# Mobile_Tracker_Hat.net
KiCad netlist of a schematic drawn in Altium Designer
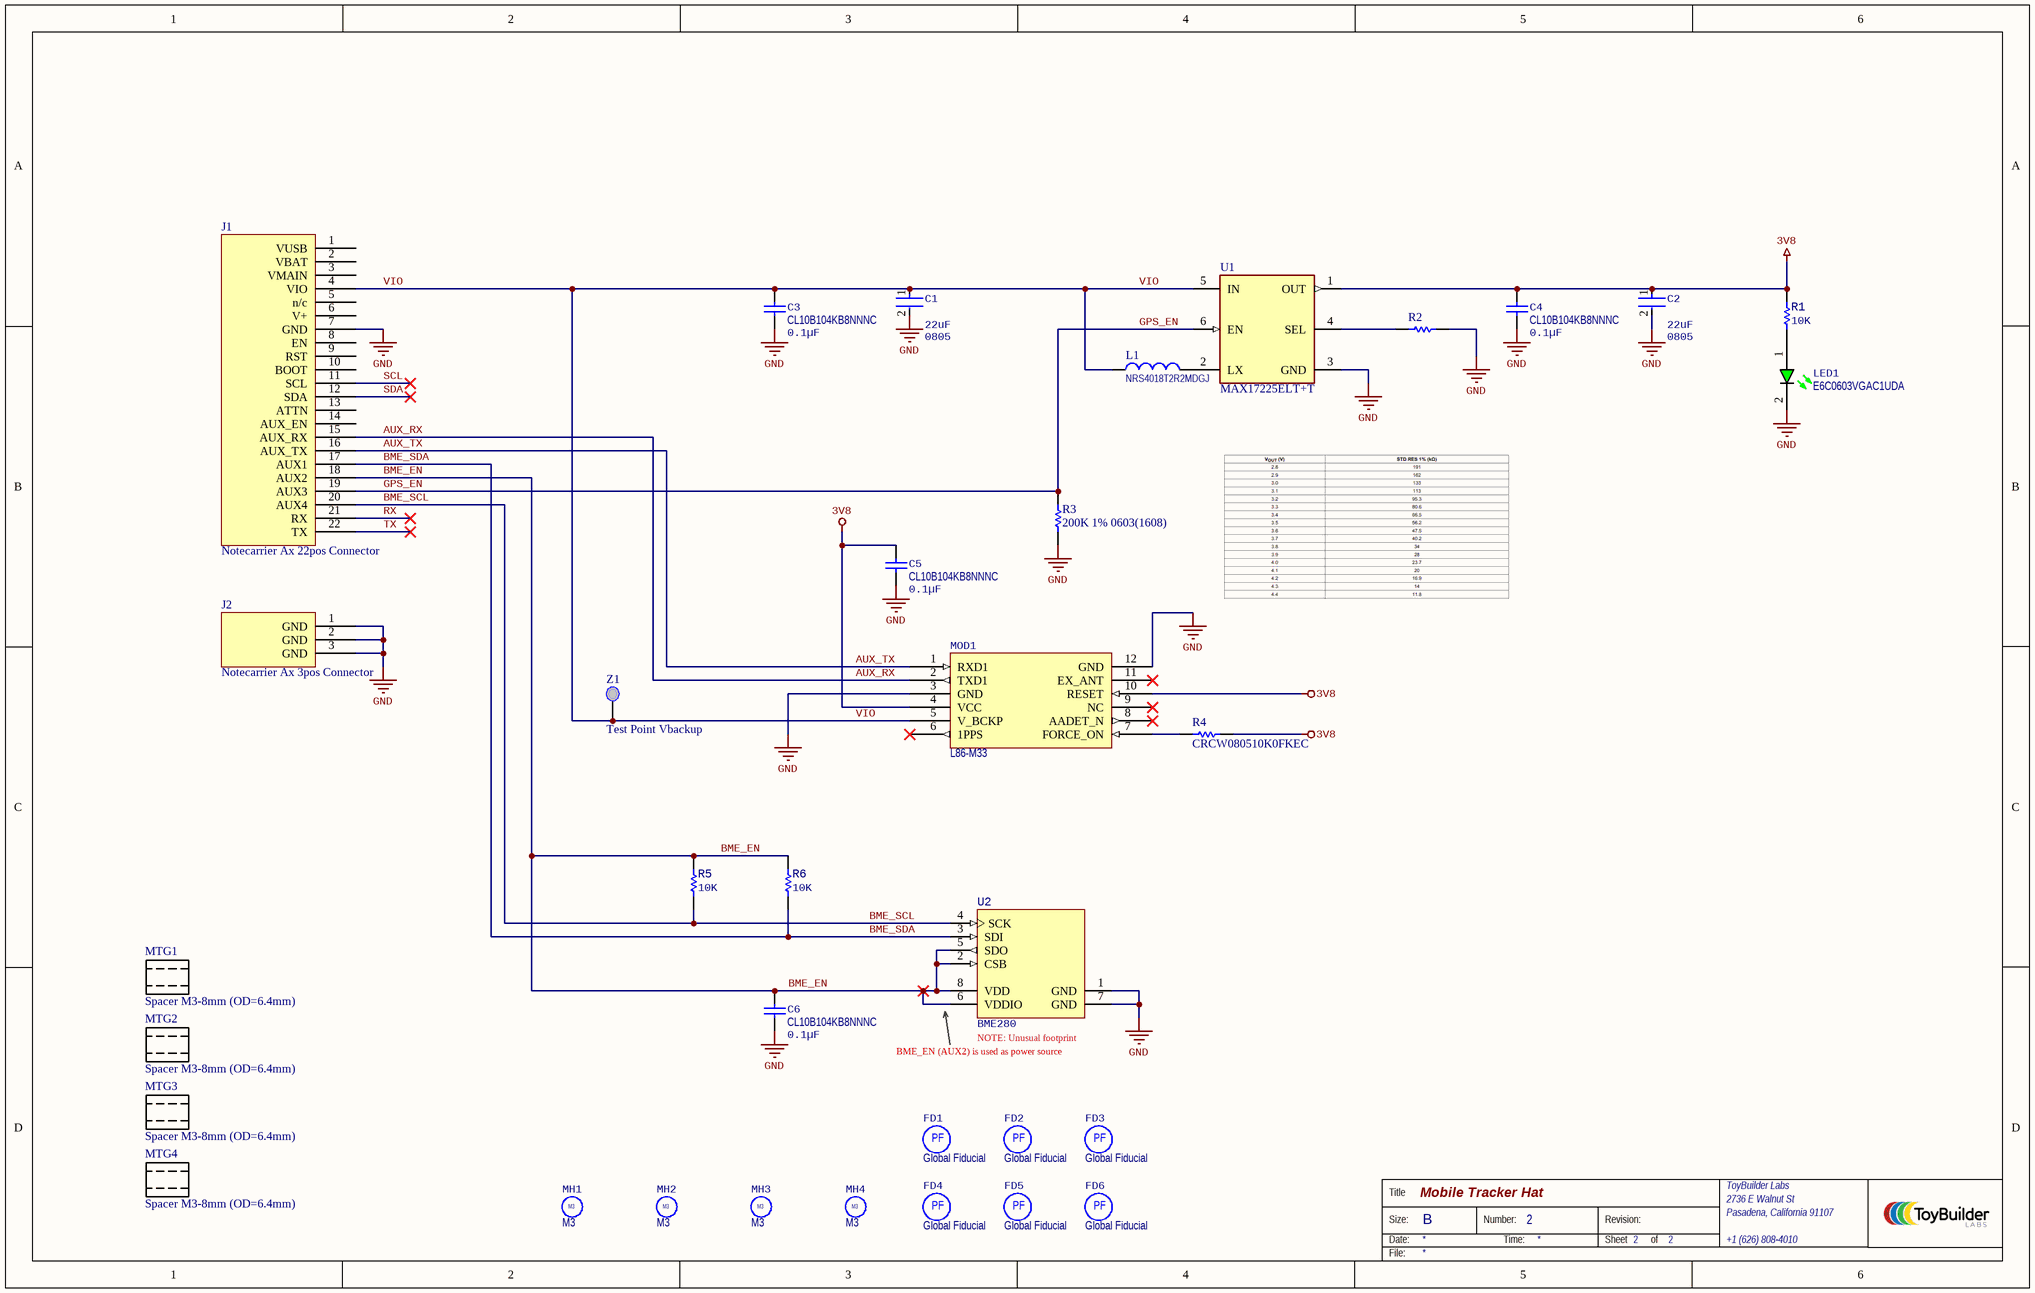
[diagram p0: Mobile Tracker Hat.SchDoc]

(export (version "E")
  (design (tool "Eeschema 10.0.6"))
  (components
    (comp (ref "C1")
      (value "CL21A226MQQNNNE")
      (footprint "FP-CL21-IPC_A")
      (description "CL21 Series 0805 22uF 6.3V ±20% Tolerance X5R Multilayer Ceramic Chip Capacitor")
      (fields
        (field (name "CAPACITANCE") "22uF")
        (field (name "CASE CODE (IMPERIAL)") "0805")
        (field (name "TOLERANCE") "20%")
      )
      (libsource (lib "Altium Content Vault") (part "b4654b650e69147ec39a6b967a45e02"))
    )
    (comp (ref "C2")
      (value "CL21A226MQQNNNE")
      (footprint "FP-CL21-IPC_A")
      (description "CL21 Series 0805 22uF 6.3V ±20% Tolerance X5R Multilayer Ceramic Chip Capacitor")
      (fields
        (field (name "CAPACITANCE") "22uF")
        (field (name "CASE CODE (IMPERIAL)") "0805")
        (field (name "TOLERANCE") "20%")
      )
      (libsource (lib "Altium Content Vault") (part "b4654b650e69147ec39a6b967a45e02"))
    )
    (comp (ref "C3")
      (value "CL10B104KB8NNNC")
      (footprint "SAMS-C0603-2_M")
      (description "Multi-layer Ceramic Capacitor, -55 to 125 degC, 2-Pin SMD (0603), RoHS, Tape and Reel")
      (fields
        (field (name "CAPACITANCE") "0.1µF")
        (field (name "MANUFACTURER") "Samsung Electro-Mechanics")
        (field (name "TOLERANCE") "10%")
      )
      (libsource (lib "Altium Content Vault") (part "CAP-NP-2"))
    )
    (comp (ref "C4")
      (value "CL10B104KB8NNNC")
      (footprint "SAMS-C0603-2_M")
      (description "Multi-layer Ceramic Capacitor, -55 to 125 degC, 2-Pin SMD (0603), RoHS, Tape and Reel")
      (fields
        (field (name "CAPACITANCE") "0.1µF")
        (field (name "MANUFACTURER") "Samsung Electro-Mechanics")
        (field (name "TOLERANCE") "10%")
      )
      (libsource (lib "Altium Content Vault") (part "CAP-NP-2"))
    )
    (comp (ref "C5")
      (value "CL10B104KB8NNNC")
      (footprint "SAMS-C0603-2_M")
      (description "Multi-layer Ceramic Capacitor, -55 to 125 degC, 2-Pin SMD (0603), RoHS, Tape and Reel")
      (fields
        (field (name "CAPACITANCE") "0.1µF")
        (field (name "MANUFACTURER") "Samsung Electro-Mechanics")
        (field (name "TOLERANCE") "10%")
      )
      (libsource (lib "Altium Content Vault") (part "CAP-NP-2"))
    )
    (comp (ref "C6")
      (value "CL10B104KB8NNNC")
      (footprint "SAMS-C0603-2_M")
      (description "Multi-layer Ceramic Capacitor, -55 to 125 degC, 2-Pin SMD (0603), RoHS, Tape and Reel")
      (fields
        (field (name "CAPACITANCE") "0.1µF")
        (field (name "MANUFACTURER") "Samsung Electro-Mechanics")
        (field (name "TOLERANCE") "10%")
      )
      (libsource (lib "Altium Content Vault") (part "CAP-NP-2"))
    )
    (comp (ref "FD1")
      (value "Global Fiducial")
      (footprint "FID_1mm_3mm")
      (description "Fiducial, Global")
      (libsource (lib "TBL Common") (part "Fiducial_Global"))
    )
    (comp (ref "FD2")
      (value "Global Fiducial")
      (footprint "FID_1mm_3mm")
      (description "Fiducial, Global")
      (libsource (lib "TBL Common") (part "Fiducial_Global"))
    )
    (comp (ref "FD3")
      (value "Global Fiducial")
      (footprint "FID_1mm_3mm")
      (description "Fiducial, Global")
      (libsource (lib "TBL Common") (part "Fiducial_Global"))
    )
    (comp (ref "FD4")
      (value "Global Fiducial")
      (footprint "FID_1mm_3mm")
      (description "Fiducial, Global")
      (libsource (lib "TBL Common") (part "Fiducial_Global"))
    )
    (comp (ref "FD5")
      (value "Global Fiducial")
      (footprint "FID_1mm_3mm")
      (description "Fiducial, Global")
      (libsource (lib "TBL Common") (part "Fiducial_Global"))
    )
    (comp (ref "FD6")
      (value "Global Fiducial")
      (footprint "FID_1mm_3mm")
      (description "Fiducial, Global")
      (libsource (lib "TBL Common") (part "Fiducial_Global"))
    )
    (comp (ref "J1")
      (value "Notecarrier Ax 22pos Connector")
      (footprint "HDR-NC-AX-22_4UCON")
      (description "Header, 22 pos. For connection to Notecarrier Ax.")
      (fields (field (name "MANUFACTURER") "4UCON") (field (name "MANUFACTURER PART NUMBER") "22042"))
      (libsource (lib "NC-A GPS Hat") (part "HDR-NC-AX-22_4UCON"))
    )
    (comp (ref "J2")
      (value "Notecarrier Ax 3pos Connector")
      (footprint "HDR-NC-AX-3_4UCON")
      (description "Header, 3 pos. For connection to Notecarrier Ax.")
      (fields (field (name "MANUFACTURER") "4UCON") (field (name "MANUFACTURER PART NUMBER") "00626"))
      (libsource (lib "NC-A GPS Hat") (part "HDR-NC-AX-3_4UCON"))
    )
    (comp (ref "L1")
      (value "NRS4018T2R2MDGJ")
      (footprint "COIL_4040x18")
      (description "2.2uH, 2.20A, SMD (4.0 x 4.0mm, 1.8 mm high)")
      (fields (field (name "MANUFACTURER") "Taiyo Yuden") (field (name "TOLERANCE") "20%"))
      (libsource (lib "TBL Inductors") (part "TAIYO_NRS4018T2R2MDGJ"))
    )
    (comp (ref "LED1")
      (value "E6C0603VGAC1UDA")
      (footprint "E6C0603VGAC1UDA")
      (description "Green 520nm 800mcd @ 20mA, 1.6 x 0.8 mm")
      (fields (field (name "MANUFACTURER") "EKINGLUX"))
      (libsource (lib "TBL Miscellaneous LEDs") (part "E6C0603VGAC1UDA"))
    )
    (comp (ref "MH1")
      (value "M3")
      (footprint "HOLE_3MM")
      (description "Bare Hole, M3")
      (libsource (lib "TBL Mechanical") (part "Bare Hole M3"))
    )
    (comp (ref "MH2")
      (value "M3")
      (footprint "HOLE_3MM")
      (description "Bare Hole, M3")
      (libsource (lib "TBL Mechanical") (part "Bare Hole M3"))
    )
    (comp (ref "MH3")
      (value "M3")
      (footprint "HOLE_3MM")
      (description "Bare Hole, M3")
      (libsource (lib "TBL Mechanical") (part "Bare Hole M3"))
    )
    (comp (ref "MH4")
      (value "M3")
      (footprint "HOLE_3MM")
      (description "Bare Hole, M3")
      (libsource (lib "TBL Mechanical") (part "Bare Hole M3"))
    )
    (comp (ref "MOD1")
      (value "L86-M33")
      (footprint "Quectel L86")
      (description "Global Navigation Satellite System Module with Patch Antenna. Quectel L86-M33")
      (libsource (lib "NC-A GPS Hat") (part "L86-M33"))
    )
    (comp (ref "MTG1")
      (value "Spacer M3-8mm (OD=6.4mm)")
      (footprint "SPACER_M3_8MM (4.75 OD)")
      (description "Spacer, non-threaded. M3 ID, 6.4mm OD.  L=8mm")
      (libsource (lib "TBL Mechanical") (part "SPACER_M3_8MM (6.40 OD)"))
    )
    (comp (ref "MTG2")
      (value "Spacer M3-8mm (OD=6.4mm)")
      (footprint "SPACER_M3_8MM (4.75 OD)")
      (description "Spacer, non-threaded. M3 ID, 6.4mm OD.  L=8mm")
      (libsource (lib "TBL Mechanical") (part "SPACER_M3_8MM (6.40 OD)"))
    )
    (comp (ref "MTG3")
      (value "Spacer M3-8mm (OD=6.4mm)")
      (footprint "SPACER_M3_8MM (4.75 OD)")
      (description "Spacer, non-threaded. M3 ID, 6.4mm OD.  L=8mm")
      (libsource (lib "TBL Mechanical") (part "SPACER_M3_8MM (6.40 OD)"))
    )
    (comp (ref "MTG4")
      (value "Spacer M3-8mm (OD=6.4mm)")
      (footprint "SPACER_M3_8MM (4.75 OD)")
      (description "Spacer, non-threaded. M3 ID, 6.4mm OD.  L=8mm")
      (libsource (lib "TBL Mechanical") (part "SPACER_M3_8MM (6.40 OD)"))
    )
    (comp (ref "R1")
      (value "10K")
      (footprint "RESC0603(1608)_N")
      (description "10K 0.1W 5% 0603 (1608 Metric)  SMD")
      (fields (field (name "TOLERANCE") "5 %") (field (name "POWER") "0.1 W"))
      (libsource (lib "Altium Content Vault") (part "RES"))
    )
    (comp (ref "R2")
      (value "CRCW060334K0FKEA")
      (footprint "RESC1609X50X30ML10T20")
      (description "Res SMD 0603 34K Ohm 1% 1/10W")
      (libsource (lib "ToyBuilder Labs") (part "RES"))
    )
    (comp (ref "R3")
      (value "200K 1% 0603(1608)")
      (footprint "RESC0603(1608)_L")
      (description "200K 0.1W 1% 0603 (1608 Metric)  SMD")
      (fields (field (name "TOLERANCE") "1 %") (field (name "POWER") "0.1 W"))
      (libsource (lib "ToyBuilder Labs") (part "RES"))
    )
    (comp (ref "R4")
      (value "CRCW080510K0FKEC")
      (footprint "RESC2013X50X30NL20T20")
      (description "Res SMD 0805 10K Ohm 1% 1/8W")
      (libsource (lib "ToyBuilder Labs") (part "RES"))
    )
    (comp (ref "R5")
      (value "10K")
      (footprint "RESC0603(1608)_N")
      (description "10K 0.1W 5% 0603 (1608 Metric)  SMD")
      (fields (field (name "TOLERANCE") "5 %") (field (name "POWER") "0.1 W"))
      (libsource (lib "Altium Content Vault") (part "RES"))
    )
    (comp (ref "R6")
      (value "10K")
      (footprint "RESC0603(1608)_N")
      (description "10K 0.1W 5% 0603 (1608 Metric)  SMD")
      (fields (field (name "TOLERANCE") "5 %") (field (name "POWER") "0.1 W"))
      (libsource (lib "Altium Content Vault") (part "RES"))
    )
    (comp (ref "U1")
      (value "MAX17225ELT+T")
      (footprint "FP-L622-1C-MFG")
      (description "Switching Voltage Regulators 0.9V to 5V, 500mA Input Current Limit Ultra Low Pow")
      (libsource (lib "ToyBuilder Labs") (part "2bed608bb5401b434f83e5ce80fdaca"))
    )
    (comp (ref "U2")
      (value "BME280")
      (footprint "BOSC-BME280-8_V")
      (fields (field (name "MANUFACTURER") "Bosch Sensortec"))
      (libsource (lib "Altium Content Vault") (part "CMP-2000-05073-1"))
    )
    (comp (ref "Z1")
      (value "Test Point Vbackup")
      (footprint "testp_40pad")
      (description "Test point")
      (libsource (lib "TBL Common") (part "test_pt"))
    )
  )
  (nets
    (net (code "1") (name "/AUX_RX") (class "Default")
      (node (ref "J1") (pin "15") (pinfunction "AUX_RX_15") (pintype "passive"))
      (node (ref "MOD1") (pin "2") (pinfunction "TXD1_2") (pintype "output"))
    )
    (net (code "2") (name "/AUX_TX") (class "Default")
      (node (ref "J1") (pin "16") (pinfunction "AUX_TX_16") (pintype "passive"))
      (node (ref "MOD1") (pin "1") (pinfunction "RXD1_1") (pintype "input"))
    )
    (net (code "3") (name "/BME_EN") (class "Default")
      (node (ref "C6") (pin "2") (pinfunction "2_2") (pintype "passive"))
      (node (ref "J1") (pin "18") (pinfunction "AUX2_18") (pintype "passive"))
      (node (ref "R5") (pin "2") (pinfunction "2_2") (pintype "passive"))
      (node (ref "R6") (pin "2") (pinfunction "2_2") (pintype "passive"))
      (node (ref "U2") (pin "2") (pinfunction "CSB_2") (pintype "input"))
      (node (ref "U2") (pin "5") (pinfunction "SDO_5") (pintype "output"))
      (node (ref "U2") (pin "6") (pinfunction "VDDIO_6") (pintype "power_in"))
      (node (ref "U2") (pin "8") (pinfunction "VDD_8") (pintype "power_in"))
    )
    (net (code "4") (name "/BME_SCL") (class "Default")
      (node (ref "J1") (pin "20") (pinfunction "AUX4_20") (pintype "passive"))
      (node (ref "R5") (pin "1") (pinfunction "1_1") (pintype "passive"))
      (node (ref "U2") (pin "4") (pinfunction "SCK_4") (pintype "input"))
    )
    (net (code "5") (name "/BME_SDA") (class "Default")
      (node (ref "J1") (pin "17") (pinfunction "AUX1_17") (pintype "passive"))
      (node (ref "R6") (pin "1") (pinfunction "1_1") (pintype "passive"))
      (node (ref "U2") (pin "3") (pinfunction "SDI_3") (pintype "input"))
    )
    (net (code "6") (name "/GPS_EN") (class "Default")
      (node (ref "J1") (pin "19") (pinfunction "AUX3_19") (pintype "passive"))
      (node (ref "R3") (pin "2") (pinfunction "2_2") (pintype "passive"))
      (node (ref "U1") (pin "6") (pinfunction "EN_6") (pintype "input"))
    )
    (net (code "7") (name "/RX") (class "Default")
      (node (ref "J1") (pin "21") (pinfunction "RX_21") (pintype "passive+no_connect"))
    )
    (net (code "8") (name "/SCL") (class "Default")
      (node (ref "J1") (pin "11") (pinfunction "SCL_11") (pintype "passive+no_connect"))
    )
    (net (code "9") (name "/SDA") (class "Default")
      (node (ref "J1") (pin "12") (pinfunction "SDA_12") (pintype "passive+no_connect"))
    )
    (net (code "10") (name "/TX") (class "Default")
      (node (ref "J1") (pin "22") (pinfunction "TX_22") (pintype "passive+no_connect"))
    )
    (net (code "11") (name "/VIO") (class "Default")
      (node (ref "C1") (pin "1") (pinfunction "1_1") (pintype "passive"))
      (node (ref "C3") (pin "2") (pinfunction "2_2") (pintype "passive"))
      (node (ref "J1") (pin "4") (pinfunction "VIO_4") (pintype "passive"))
      (node (ref "L1") (pin "1") (pinfunction "1_1") (pintype "passive"))
      (node (ref "MOD1") (pin "5") (pinfunction "V_BCKP_5") (pintype "passive"))
      (node (ref "U1") (pin "5") (pinfunction "IN_5") (pintype "power_in"))
      (node (ref "Z1") (pin "1") (pinfunction "1_1") (pintype "passive"))
    )
    (net (code "12") (name "3V8") (class "Default")
      (node (ref "C2") (pin "1") (pinfunction "1_1") (pintype "passive"))
      (node (ref "C4") (pin "2") (pinfunction "2_2") (pintype "passive"))
      (node (ref "C5") (pin "2") (pinfunction "2_2") (pintype "passive"))
      (node (ref "MOD1") (pin "10") (pinfunction "RESET_10") (pintype "input"))
      (node (ref "MOD1") (pin "4") (pinfunction "VCC_4") (pintype "passive"))
      (node (ref "R1") (pin "2") (pinfunction "2_2") (pintype "passive"))
      (node (ref "R4") (pin "2") (pinfunction "2_2") (pintype "passive"))
      (node (ref "U1") (pin "1") (pinfunction "OUT_1") (pintype "output"))
    )
    (net (code "13") (name "GND") (class "Default")
      (node (ref "C1") (pin "2") (pinfunction "2_2") (pintype "passive"))
      (node (ref "C2") (pin "2") (pinfunction "2_2") (pintype "passive"))
      (node (ref "C3") (pin "1") (pinfunction "1_1") (pintype "passive"))
      (node (ref "C4") (pin "1") (pinfunction "1_1") (pintype "passive"))
      (node (ref "C5") (pin "1") (pinfunction "1_1") (pintype "passive"))
      (node (ref "C6") (pin "1") (pinfunction "1_1") (pintype "passive"))
      (node (ref "J1") (pin "7") (pinfunction "GND_7") (pintype "passive"))
      (node (ref "J2") (pin "1") (pinfunction "GND_1") (pintype "passive"))
      (node (ref "J2") (pin "2") (pinfunction "GND_2") (pintype "passive"))
      (node (ref "J2") (pin "3") (pinfunction "GND_3") (pintype "passive"))
      (node (ref "LED1") (pin "2") (pinfunction "K_2") (pintype "passive"))
      (node (ref "MOD1") (pin "12") (pinfunction "GND_12") (pintype "passive"))
      (node (ref "MOD1") (pin "3") (pinfunction "GND_3") (pintype "passive"))
      (node (ref "R2") (pin "2") (pinfunction "2_2") (pintype "passive"))
      (node (ref "R3") (pin "1") (pinfunction "1_1") (pintype "passive"))
      (node (ref "U1") (pin "3") (pinfunction "GND_3") (pintype "power_in"))
      (node (ref "U2") (pin "1") (pinfunction "GND_1") (pintype "power_in"))
      (node (ref "U2") (pin "7") (pinfunction "GND_7") (pintype "power_in"))
    )
    (net (code "14") (name "Net-(LED1-A)") (class "Default")
      (node (ref "LED1") (pin "1") (pinfunction "A_1") (pintype "passive"))
      (node (ref "R1") (pin "1") (pinfunction "1_1") (pintype "passive"))
    )
    (net (code "15") (name "Net-(MOD1-FORCE_ON)") (class "Default")
      (node (ref "MOD1") (pin "7") (pinfunction "FORCE_ON_7") (pintype "input"))
      (node (ref "R4") (pin "1") (pinfunction "1_1") (pintype "passive"))
    )
    (net (code "16") (name "Net-(U1-LX)") (class "Default")
      (node (ref "L1") (pin "2") (pinfunction "2_2") (pintype "passive"))
      (node (ref "U1") (pin "2") (pinfunction "LX_2") (pintype "passive"))
    )
    (net (code "17") (name "Net-(U1-SEL)") (class "Default")
      (node (ref "R2") (pin "1") (pinfunction "1_1") (pintype "passive"))
      (node (ref "U1") (pin "4") (pinfunction "SEL_4") (pintype "passive"))
    )
    (net (code "18") (name "unconnected-(J1-ATTN-Pad13)") (class "Default")
      (node (ref "J1") (pin "13") (pinfunction "ATTN_13") (pintype "passive"))
    )
    (net (code "19") (name "unconnected-(J1-AUX_EN-Pad14)") (class "Default")
      (node (ref "J1") (pin "14") (pinfunction "AUX_EN_14") (pintype "passive"))
    )
    (net (code "20") (name "unconnected-(J1-BOOT-Pad10)") (class "Default")
      (node (ref "J1") (pin "10") (pinfunction "BOOT_10") (pintype "passive"))
    )
    (net (code "21") (name "unconnected-(J1-EN-Pad8)") (class "Default")
      (node (ref "J1") (pin "8") (pinfunction "EN_8") (pintype "passive"))
    )
    (net (code "22") (name "unconnected-(J1-RST-Pad9)") (class "Default")
      (node (ref "J1") (pin "9") (pinfunction "RST_9") (pintype "passive"))
    )
    (net (code "23") (name "unconnected-(J1-V+-Pad6)") (class "Default")
      (node (ref "J1") (pin "6") (pinfunction "V+_6") (pintype "passive"))
    )
    (net (code "24") (name "unconnected-(J1-VBAT-Pad2)") (class "Default")
      (node (ref "J1") (pin "2") (pinfunction "VBAT_2") (pintype "passive"))
    )
    (net (code "25") (name "unconnected-(J1-VMAIN-Pad3)") (class "Default")
      (node (ref "J1") (pin "3") (pinfunction "VMAIN_3") (pintype "passive"))
    )
    (net (code "26") (name "unconnected-(J1-VUSB-Pad1)") (class "Default")
      (node (ref "J1") (pin "1") (pinfunction "VUSB_1") (pintype "passive"))
    )
    (net (code "27") (name "unconnected-(J1-n{slash}c-Pad5)") (class "Default")
      (node (ref "J1") (pin "5") (pinfunction "n/c_5") (pintype "passive"))
    )
    (net (code "28") (name "unconnected-(MOD1-1PPS-Pad6)") (class "Default")
      (node (ref "MOD1") (pin "6") (pinfunction "1PPS_6") (pintype "output+no_connect"))
    )
    (net (code "29") (name "unconnected-(MOD1-AADET_N-Pad8)") (class "Default")
      (node (ref "MOD1") (pin "8") (pinfunction "AADET_N_8") (pintype "output+no_connect"))
    )
    (net (code "30") (name "unconnected-(MOD1-EX_ANT-Pad11)") (class "Default")
      (node (ref "MOD1") (pin "11") (pinfunction "EX_ANT_11") (pintype "passive+no_connect"))
    )
    (net (code "31") (name "unconnected-(MOD1-NC-Pad9)") (class "Default")
      (node (ref "MOD1") (pin "9") (pinfunction "NC_9") (pintype "passive+no_connect"))
    )
  )
)
